# Power.net
KiCad netlist of a schematic drawn in Altium Designer
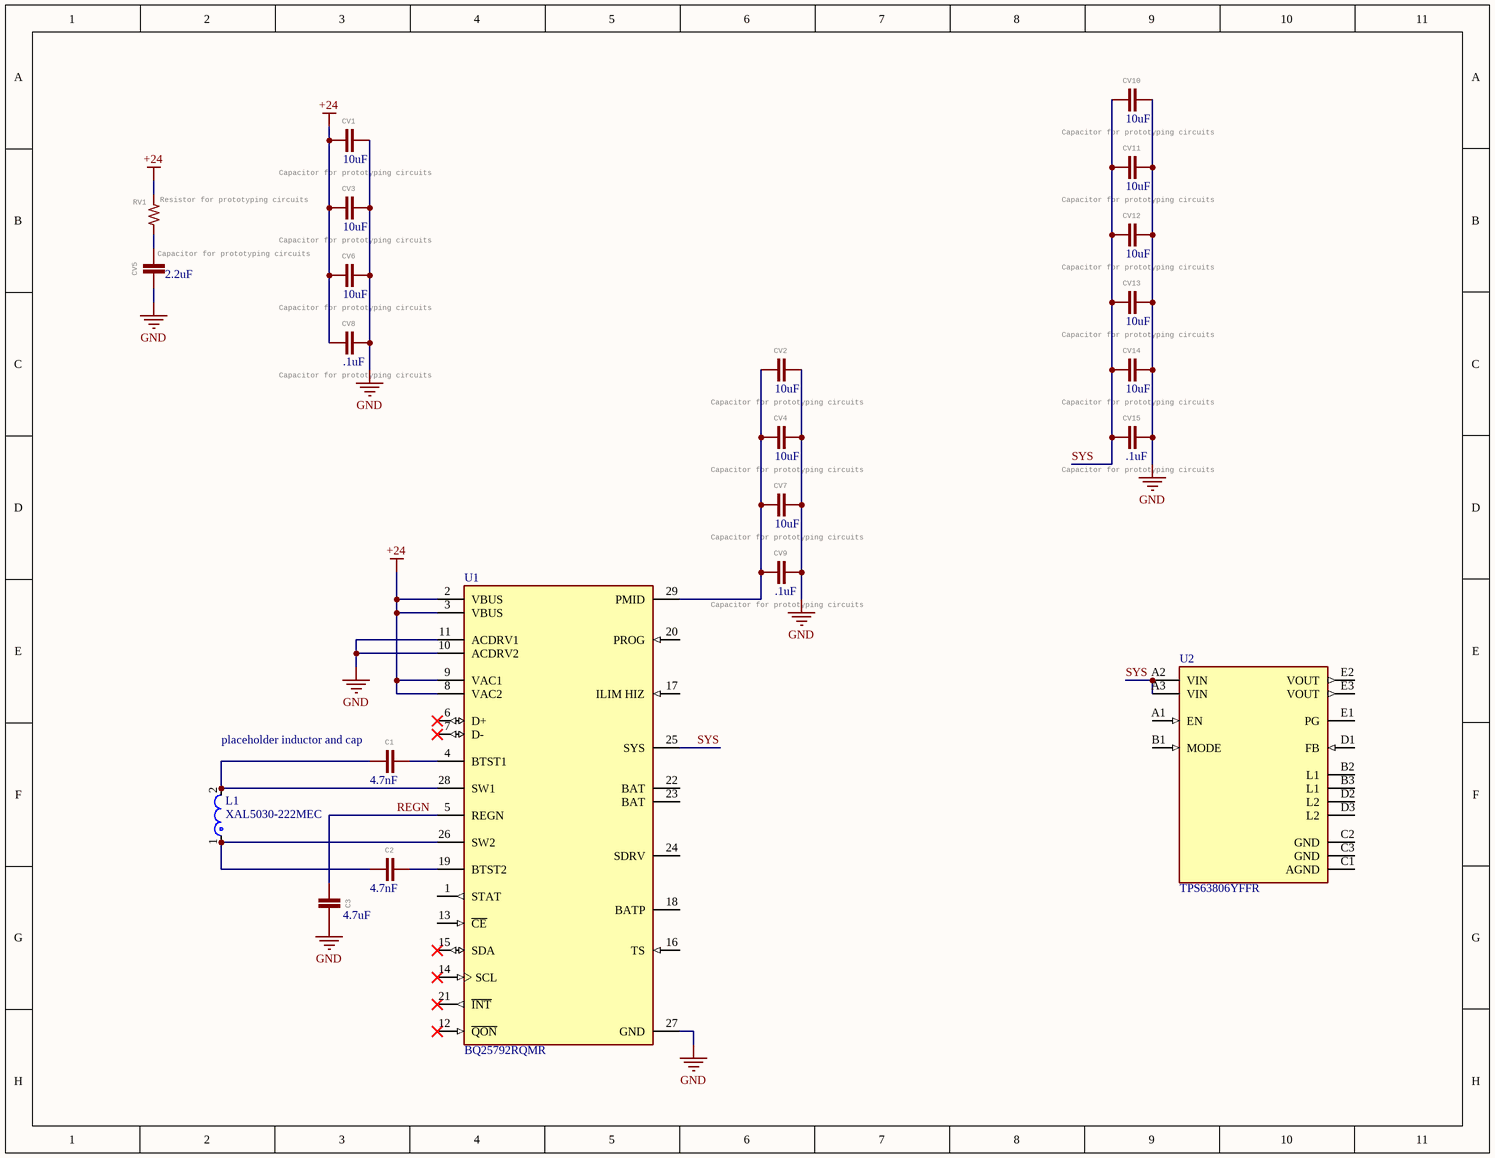
[diagram p0: Power.SchDoc]

(export (version "E")
  (design (tool "Eeschema 10.0.6"))
  (components
    (comp (ref "C1")
      (value "Capacitor, Non-Polarized  VJ...1BC Series Datasheet  Samsung Datasheet  Walsin Datasheet  GRM188R61A226ME15D  GRM188R61E106MA73D  885012006013  2220Y6300105KXTWS2  Yageo Class 2, X5R  TDK C Series  AVX Automotive MLCC   KEMET X7R Series  Kyocera AVX  GRM21BR61H  C1812W104KDRACTU")
      (footprint "0805-CAP")
      (fields
        (field (name "MANUFACTURER") "KEMET")
        (field (name "MPN") "C0805C224K1RACTU")
        (field (name "TOLERANCE") "10%")
        (field (name "CAPACITANCE") "4.7nF")
      )
      (libsource (lib "HyTechDevices") (part "CAPACITOR_?_*0805"))
    )
    (comp (ref "C2")
      (value "Capacitor, Non-Polarized  VJ...1BC Series Datasheet  Samsung Datasheet  Walsin Datasheet  GRM188R61A226ME15D  GRM188R61E106MA73D  885012006013  2220Y6300105KXTWS2  Yageo Class 2, X5R  TDK C Series  AVX Automotive MLCC   KEMET X7R Series  Kyocera AVX  GRM21BR61H  C1812W104KDRACTU")
      (footprint "0805-CAP")
      (fields
        (field (name "MANUFACTURER") "KEMET")
        (field (name "MPN") "C0805C224K1RACTU")
        (field (name "TOLERANCE") "10%")
        (field (name "CAPACITANCE") "4.7nF")
      )
      (libsource (lib "HyTechDevices") (part "CAPACITOR_?_*0805"))
    )
    (comp (ref "C3")
      (value "Capacitor, Non-Polarized  VJ...1BC Series Datasheet  Samsung Datasheet  Walsin Datasheet  GRM188R61A226ME15D  GRM188R61E106MA73D  885012006013  2220Y6300105KXTWS2  Yageo Class 2, X5R  TDK C Series  AVX Automotive MLCC   KEMET X7R Series  Kyocera AVX  GRM21BR61H  C1812W104KDRACTU")
      (footprint "0805-CAP")
      (fields
        (field (name "MANUFACTURER") "KEMET")
        (field (name "MPN") "C0805C224K1RACTU")
        (field (name "TOLERANCE") "10%")
        (field (name "CAPACITANCE") "4.7uF")
      )
      (libsource (lib "") (part "CAPACITOR_?_*0805_1"))
    )
    (comp (ref "CV1")
      (value "Capacitor for prototyping circuits")
      (footprint "0603-CAP")
      (fields (field (name "CAPACITANCE") "10uF"))
      (libsource (lib "HyTechDevices") (part "CAPACITOR_VALUE"))
    )
    (comp (ref "CV2")
      (value "Capacitor for prototyping circuits")
      (footprint "0603-CAP")
      (fields (field (name "CAPACITANCE") "10uF"))
      (libsource (lib "HyTechDevices") (part "CAPACITOR_VALUE"))
    )
    (comp (ref "CV3")
      (value "Capacitor for prototyping circuits")
      (footprint "0603-CAP")
      (fields (field (name "CAPACITANCE") "10uF"))
      (libsource (lib "HyTechDevices") (part "CAPACITOR_VALUE"))
    )
    (comp (ref "CV4")
      (value "Capacitor for prototyping circuits")
      (footprint "0603-CAP")
      (fields (field (name "CAPACITANCE") "10uF"))
      (libsource (lib "HyTechDevices") (part "CAPACITOR_VALUE"))
    )
    (comp (ref "CV5")
      (value "Capacitor for prototyping circuits")
      (footprint "0603-CAP")
      (fields (field (name "CAPACITANCE") "2.2uF"))
      (libsource (lib "") (part "CAPACITOR_VALUE_1"))
    )
    (comp (ref "CV6")
      (value "Capacitor for prototyping circuits")
      (footprint "0603-CAP")
      (fields (field (name "CAPACITANCE") "10uF"))
      (libsource (lib "HyTechDevices") (part "CAPACITOR_VALUE"))
    )
    (comp (ref "CV7")
      (value "Capacitor for prototyping circuits")
      (footprint "0603-CAP")
      (fields (field (name "CAPACITANCE") "10uF"))
      (libsource (lib "HyTechDevices") (part "CAPACITOR_VALUE"))
    )
    (comp (ref "CV8")
      (value "Capacitor for prototyping circuits")
      (footprint "0603-CAP")
      (fields (field (name "CAPACITANCE") ".1uF"))
      (libsource (lib "HyTechDevices") (part "CAPACITOR_VALUE"))
    )
    (comp (ref "CV9")
      (value "Capacitor for prototyping circuits")
      (footprint "0603-CAP")
      (fields (field (name "CAPACITANCE") ".1uF"))
      (libsource (lib "HyTechDevices") (part "CAPACITOR_VALUE"))
    )
    (comp (ref "CV10")
      (value "Capacitor for prototyping circuits")
      (footprint "0603-CAP")
      (fields (field (name "CAPACITANCE") "10uF"))
      (libsource (lib "HyTechDevices") (part "CAPACITOR_VALUE"))
    )
    (comp (ref "CV11")
      (value "Capacitor for prototyping circuits")
      (footprint "0603-CAP")
      (fields (field (name "CAPACITANCE") "10uF"))
      (libsource (lib "HyTechDevices") (part "CAPACITOR_VALUE"))
    )
    (comp (ref "CV12")
      (value "Capacitor for prototyping circuits")
      (footprint "0603-CAP")
      (fields (field (name "CAPACITANCE") "10uF"))
      (libsource (lib "HyTechDevices") (part "CAPACITOR_VALUE"))
    )
    (comp (ref "CV13")
      (value "Capacitor for prototyping circuits")
      (footprint "0603-CAP")
      (fields (field (name "CAPACITANCE") "10uF"))
      (libsource (lib "HyTechDevices") (part "CAPACITOR_VALUE"))
    )
    (comp (ref "CV14")
      (value "Capacitor for prototyping circuits")
      (footprint "0603-CAP")
      (fields (field (name "CAPACITANCE") "10uF"))
      (libsource (lib "HyTechDevices") (part "CAPACITOR_VALUE"))
    )
    (comp (ref "CV15")
      (value "Capacitor for prototyping circuits")
      (footprint "0603-CAP")
      (fields (field (name "CAPACITANCE") ".1uF"))
      (libsource (lib "HyTechDevices") (part "CAPACITOR_VALUE"))
    )
    (comp (ref "L1")
      (value "XAL5030-222MEC")
      (footprint "FP-XAL5030-222MEC-MFG")
      (description "Fixed Inductors 2.2uH Shld 20% 9.2A 14.5mOhms AECQ2 SRF: 38MHz Test Freq: 1MHz")
      (fields (field (name "TOLERANCE") "20%"))
      (libsource (lib "Altium Content Vault") (part "4cc4b267dca4c8e51f7102f422741d8"))
    )
    (comp (ref "RV1")
      (value "Resistor for prototyping circuits")
      (footprint "0603-RES")
      (libsource (lib "HyTechDevices") (part "RESISTOR_VALUE"))
    )
    (comp (ref "U1")
      (value "BQ25792RQMR")
      (footprint "FP-RQM0029A-MFG")
      (description "Power Supply Management Circuit, Adjustable, 1 Channel, 3.4, PQCC29")
      (fields (field (name "MANUFACTURER") "Texas Instruments"))
      (libsource (lib "CM4") (part "BQ25792RQMR"))
    )
    (comp (ref "U2")
      (value "TPS63806YFFR")
      (footprint "FP-YFF0015-IPC_C")
      (description "Switching Regulator, Current-mode, 2.5A, 3100kHz Switching Freq-Max, PBGA15")
      (fields (field (name "MANUFACTURER") "Texas Instruments"))
      (libsource (lib "CM4") (part "TPS63806YFFR"))
    )
  )
  (nets
    (net (code "1") (name "+24") (class "Default")
      (node (ref "CV1") (pin "2") (pinfunction "2_2") (pintype "passive"))
      (node (ref "CV3") (pin "2") (pinfunction "2_2") (pintype "passive"))
      (node (ref "CV6") (pin "2") (pinfunction "2_2") (pintype "passive"))
      (node (ref "CV8") (pin "2") (pinfunction "2_2") (pintype "passive"))
      (node (ref "RV1") (pin "2") (pinfunction "2_2") (pintype "passive"))
      (node (ref "U1") (pin "2") (pinfunction "VBUS_2") (pintype "power_in"))
      (node (ref "U1") (pin "3") (pinfunction "VBUS_3") (pintype "power_in"))
      (node (ref "U1") (pin "8") (pinfunction "VAC2_8") (pintype "power_in"))
      (node (ref "U1") (pin "9") (pinfunction "VAC1_9") (pintype "power_in"))
    )
    (net (code "2") (name "/REGN") (class "Default")
      (node (ref "C3") (pin "2") (pinfunction "2_2") (pintype "passive"))
      (node (ref "U1") (pin "5") (pinfunction "REGN_5") (pintype "power_in"))
    )
    (net (code "3") (name "/SYS") (class "Default")
      (node (ref "CV10") (pin "2") (pinfunction "2_2") (pintype "passive"))
      (node (ref "CV11") (pin "2") (pinfunction "2_2") (pintype "passive"))
      (node (ref "CV12") (pin "2") (pinfunction "2_2") (pintype "passive"))
      (node (ref "CV13") (pin "2") (pinfunction "2_2") (pintype "passive"))
      (node (ref "CV14") (pin "2") (pinfunction "2_2") (pintype "passive"))
      (node (ref "CV15") (pin "2") (pinfunction "2_2") (pintype "passive"))
      (node (ref "U1") (pin "25") (pinfunction "SYS_25") (pintype "power_in"))
      (node (ref "U2") (pin "A2") (pinfunction "VIN_A2") (pintype "power_in"))
      (node (ref "U2") (pin "A3") (pinfunction "VIN_A3") (pintype "power_in"))
    )
    (net (code "4") (name "GND") (class "Default")
      (node (ref "C3") (pin "1") (pinfunction "1_1") (pintype "passive"))
      (node (ref "CV1") (pin "1") (pinfunction "1_1") (pintype "passive"))
      (node (ref "CV10") (pin "1") (pinfunction "1_1") (pintype "passive"))
      (node (ref "CV11") (pin "1") (pinfunction "1_1") (pintype "passive"))
      (node (ref "CV12") (pin "1") (pinfunction "1_1") (pintype "passive"))
      (node (ref "CV13") (pin "1") (pinfunction "1_1") (pintype "passive"))
      (node (ref "CV14") (pin "1") (pinfunction "1_1") (pintype "passive"))
      (node (ref "CV15") (pin "1") (pinfunction "1_1") (pintype "passive"))
      (node (ref "CV2") (pin "1") (pinfunction "1_1") (pintype "passive"))
      (node (ref "CV3") (pin "1") (pinfunction "1_1") (pintype "passive"))
      (node (ref "CV4") (pin "1") (pinfunction "1_1") (pintype "passive"))
      (node (ref "CV5") (pin "2") (pinfunction "2_2") (pintype "passive"))
      (node (ref "CV6") (pin "1") (pinfunction "1_1") (pintype "passive"))
      (node (ref "CV7") (pin "1") (pinfunction "1_1") (pintype "passive"))
      (node (ref "CV8") (pin "1") (pinfunction "1_1") (pintype "passive"))
      (node (ref "CV9") (pin "1") (pinfunction "1_1") (pintype "passive"))
      (node (ref "U1") (pin "10") (pinfunction "ACDRV2_10") (pintype "power_in"))
      (node (ref "U1") (pin "11") (pinfunction "ACDRV1_11") (pintype "power_in"))
      (node (ref "U1") (pin "27") (pinfunction "GND_27") (pintype "power_in"))
    )
    (net (code "5") (name "Net-(CV5-Pad1)") (class "Default")
      (node (ref "CV5") (pin "1") (pinfunction "1_1") (pintype "passive"))
      (node (ref "RV1") (pin "1") (pinfunction "1_1") (pintype "passive"))
    )
    (net (code "6") (name "Net-(U1-BTST1)") (class "Default")
      (node (ref "C1") (pin "1") (pinfunction "1_1") (pintype "passive"))
      (node (ref "U1") (pin "4") (pinfunction "BTST1_4") (pintype "power_in"))
    )
    (net (code "7") (name "Net-(U1-BTST2)") (class "Default")
      (node (ref "C2") (pin "1") (pinfunction "1_1") (pintype "passive"))
      (node (ref "U1") (pin "19") (pinfunction "BTST2_19") (pintype "power_in"))
    )
    (net (code "8") (name "Net-(U1-PMID)") (class "Default")
      (node (ref "CV2") (pin "2") (pinfunction "2_2") (pintype "passive"))
      (node (ref "CV4") (pin "2") (pinfunction "2_2") (pintype "passive"))
      (node (ref "CV7") (pin "2") (pinfunction "2_2") (pintype "passive"))
      (node (ref "CV9") (pin "2") (pinfunction "2_2") (pintype "passive"))
      (node (ref "U1") (pin "29") (pinfunction "PMID_29") (pintype "power_in"))
    )
    (net (code "9") (name "Net-(U1-SW1)") (class "Default")
      (node (ref "C1") (pin "2") (pinfunction "2_2") (pintype "passive"))
      (node (ref "L1") (pin "2") (pinfunction "2_2") (pintype "passive"))
      (node (ref "U1") (pin "28") (pinfunction "SW1_28") (pintype "power_in"))
    )
    (net (code "10") (name "Net-(U1-SW2)") (class "Default")
      (node (ref "C2") (pin "2") (pinfunction "2_2") (pintype "passive"))
      (node (ref "L1") (pin "1") (pinfunction "1_1") (pintype "passive"))
      (node (ref "U1") (pin "26") (pinfunction "SW2_26") (pintype "power_in"))
    )
    (net (code "11") (name "unconnected-(U1-BAT-Pad22)") (class "Default")
      (node (ref "U1") (pin "22") (pinfunction "BAT_22") (pintype "power_in"))
    )
    (net (code "12") (name "unconnected-(U1-BAT-Pad23)") (class "Default")
      (node (ref "U1") (pin "23") (pinfunction "BAT_23") (pintype "power_in"))
    )
    (net (code "13") (name "unconnected-(U1-BATP-Pad18)") (class "Default")
      (node (ref "U1") (pin "18") (pinfunction "BATP_18") (pintype "power_in"))
    )
    (net (code "14") (name "unconnected-(U1-D+-Pad6)") (class "Default")
      (node (ref "U1") (pin "6") (pinfunction "D+_6") (pintype "bidirectional+no_connect"))
    )
    (net (code "15") (name "unconnected-(U1-D--Pad7)") (class "Default")
      (node (ref "U1") (pin "7") (pinfunction "D-_7") (pintype "bidirectional+no_connect"))
    )
    (net (code "16") (name "unconnected-(U1-ILIM_HIZ-Pad17)") (class "Default")
      (node (ref "U1") (pin "17") (pinfunction "ILIM_HIZ_17") (pintype "input"))
    )
    (net (code "17") (name "unconnected-(U1-PROG-Pad20)") (class "Default")
      (node (ref "U1") (pin "20") (pinfunction "PROG_20") (pintype "input"))
    )
    (net (code "18") (name "unconnected-(U1-SCL-Pad14)") (class "Default")
      (node (ref "U1") (pin "14") (pinfunction "SCL_14") (pintype "input+no_connect"))
    )
    (net (code "19") (name "unconnected-(U1-SDA-Pad15)") (class "Default")
      (node (ref "U1") (pin "15") (pinfunction "SDA_15") (pintype "bidirectional+no_connect"))
    )
    (net (code "20") (name "unconnected-(U1-SDRV-Pad24)") (class "Default")
      (node (ref "U1") (pin "24") (pinfunction "SDRV_24") (pintype "power_in"))
    )
    (net (code "21") (name "unconnected-(U1-STAT-Pad1)") (class "Default")
      (node (ref "U1") (pin "1") (pinfunction "STAT_1") (pintype "output"))
    )
    (net (code "22") (name "unconnected-(U1-TS-Pad16)") (class "Default")
      (node (ref "U1") (pin "16") (pinfunction "TS_16") (pintype "input"))
    )
    (net (code "23") (name "unconnected-(U1-~{CE}-Pad13)") (class "Default")
      (node (ref "U1") (pin "13") (pinfunction "~{CE}_13") (pintype "input"))
    )
    (net (code "24") (name "unconnected-(U1-~{INT}-Pad21)") (class "Default")
      (node (ref "U1") (pin "21") (pinfunction "~{INT}_21") (pintype "output+no_connect"))
    )
    (net (code "25") (name "unconnected-(U1-~{QON}-Pad12)") (class "Default")
      (node (ref "U1") (pin "12") (pinfunction "~{QON}_12") (pintype "input+no_connect"))
    )
    (net (code "26") (name "unconnected-(U2-AGND-PadC1)") (class "Default")
      (node (ref "U2") (pin "C1") (pinfunction "AGND_C1") (pintype "power_in"))
    )
    (net (code "27") (name "unconnected-(U2-EN-PadA1)") (class "Default")
      (node (ref "U2") (pin "A1") (pinfunction "EN_A1") (pintype "input"))
    )
    (net (code "28") (name "unconnected-(U2-FB-PadD1)") (class "Default")
      (node (ref "U2") (pin "D1") (pinfunction "FB_D1") (pintype "input"))
    )
    (net (code "29") (name "unconnected-(U2-GND-PadC2)") (class "Default")
      (node (ref "U2") (pin "C2") (pinfunction "GND_C2") (pintype "power_in"))
    )
    (net (code "30") (name "unconnected-(U2-GND-PadC3)") (class "Default")
      (node (ref "U2") (pin "C3") (pinfunction "GND_C3") (pintype "power_in"))
    )
    (net (code "31") (name "unconnected-(U2-L1-PadB2)") (class "Default")
      (node (ref "U2") (pin "B2") (pinfunction "L1_B2") (pintype "passive"))
    )
    (net (code "32") (name "unconnected-(U2-L1-PadB3)") (class "Default")
      (node (ref "U2") (pin "B3") (pinfunction "L1_B3") (pintype "passive"))
    )
    (net (code "33") (name "unconnected-(U2-L2-PadD2)") (class "Default")
      (node (ref "U2") (pin "D2") (pinfunction "L2_D2") (pintype "passive"))
    )
    (net (code "34") (name "unconnected-(U2-L2-PadD3)") (class "Default")
      (node (ref "U2") (pin "D3") (pinfunction "L2_D3") (pintype "passive"))
    )
    (net (code "35") (name "unconnected-(U2-MODE-PadB1)") (class "Default")
      (node (ref "U2") (pin "B1") (pinfunction "MODE_B1") (pintype "input"))
    )
    (net (code "36") (name "unconnected-(U2-PG-PadE1)") (class "Default")
      (node (ref "U2") (pin "E1") (pinfunction "PG_E1") (pintype "open_collector"))
    )
    (net (code "37") (name "unconnected-(U2-VOUT-PadE2)") (class "Default")
      (node (ref "U2") (pin "E2") (pinfunction "VOUT_E2") (pintype "output"))
    )
    (net (code "38") (name "unconnected-(U2-VOUT-PadE3)") (class "Default")
      (node (ref "U2") (pin "E3") (pinfunction "VOUT_E3") (pintype "output"))
    )
  )
)
